# Schematic.net
KiCad netlist of a schematic drawn in EAGLE
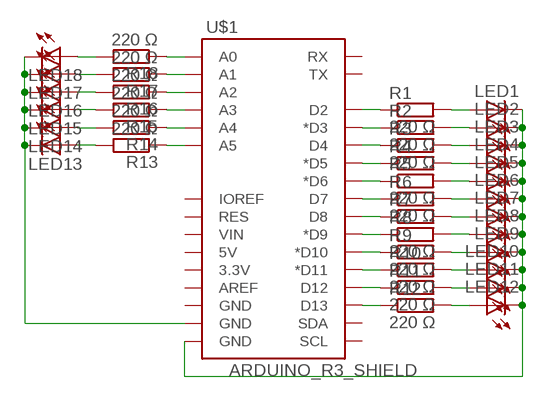
[diagram p0: schematic, sheet 1]

(export (version "E")
  (design (tool "Eeschema 10.0.6"))
  (components
    (comp (ref "LED1")
      (value "LED3MM")
      (footprint "eagle-import:LED3MM")
      (libsource (lib "eagle-import") (part "LED3MM"))
    )
    (comp (ref "LED2")
      (value "LED3MM")
      (footprint "eagle-import:LED3MM")
      (libsource (lib "eagle-import") (part "LED3MM"))
    )
    (comp (ref "LED3")
      (value "LED3MM")
      (footprint "eagle-import:LED3MM")
      (libsource (lib "eagle-import") (part "LED3MM"))
    )
    (comp (ref "LED4")
      (value "LED3MM")
      (footprint "eagle-import:LED3MM")
      (libsource (lib "eagle-import") (part "LED3MM"))
    )
    (comp (ref "LED5")
      (value "LED3MM")
      (footprint "eagle-import:LED3MM")
      (libsource (lib "eagle-import") (part "LED3MM"))
    )
    (comp (ref "LED6")
      (value "LED3MM")
      (footprint "eagle-import:LED3MM")
      (libsource (lib "eagle-import") (part "LED3MM"))
    )
    (comp (ref "LED7")
      (value "LED3MM")
      (footprint "eagle-import:LED3MM")
      (libsource (lib "eagle-import") (part "LED3MM"))
    )
    (comp (ref "LED8")
      (value "LED3MM")
      (footprint "eagle-import:LED3MM")
      (libsource (lib "eagle-import") (part "LED3MM"))
    )
    (comp (ref "LED9")
      (value "LED3MM")
      (footprint "eagle-import:LED3MM")
      (libsource (lib "eagle-import") (part "LED3MM"))
    )
    (comp (ref "LED10")
      (value "LED3MM")
      (footprint "eagle-import:LED3MM")
      (libsource (lib "eagle-import") (part "LED3MM"))
    )
    (comp (ref "LED11")
      (value "LED3MM")
      (footprint "eagle-import:LED3MM")
      (libsource (lib "eagle-import") (part "LED3MM"))
    )
    (comp (ref "LED12")
      (value "LED3MM")
      (footprint "eagle-import:LED3MM")
      (libsource (lib "eagle-import") (part "LED3MM"))
    )
    (comp (ref "LED13")
      (value "LED3MM")
      (footprint "eagle-import:LED3MM")
      (libsource (lib "eagle-import") (part "LED3MM"))
    )
    (comp (ref "LED14")
      (value "LED3MM")
      (footprint "eagle-import:LED3MM")
      (libsource (lib "eagle-import") (part "LED3MM"))
    )
    (comp (ref "LED15")
      (value "LED3MM")
      (footprint "eagle-import:LED3MM")
      (libsource (lib "eagle-import") (part "LED3MM"))
    )
    (comp (ref "LED16")
      (value "LED3MM")
      (footprint "eagle-import:LED3MM")
      (libsource (lib "eagle-import") (part "LED3MM"))
    )
    (comp (ref "LED17")
      (value "LED3MM")
      (footprint "eagle-import:LED3MM")
      (libsource (lib "eagle-import") (part "LED3MM"))
    )
    (comp (ref "LED18")
      (value "LED3MM")
      (footprint "eagle-import:LED3MM")
      (libsource (lib "eagle-import") (part "LED3MM"))
    )
    (comp (ref "R1")
      (value "220 Ω")
      (footprint "eagle-import:0204_7")
      (libsource (lib "eagle-import") (part "R-EU_0204/7"))
    )
    (comp (ref "R2")
      (value "220 Ω")
      (footprint "eagle-import:0204_7")
      (libsource (lib "eagle-import") (part "R-EU_0204/7"))
    )
    (comp (ref "R3")
      (value "220 Ω")
      (footprint "eagle-import:0204_7")
      (libsource (lib "eagle-import") (part "R-EU_0204/7"))
    )
    (comp (ref "R4")
      (value "R-EU_0204/7")
      (footprint "eagle-import:0204_7")
      (libsource (lib "eagle-import") (part "R-EU_0204/7"))
    )
    (comp (ref "R5")
      (value "220 Ω")
      (footprint "eagle-import:0204_7")
      (libsource (lib "eagle-import") (part "R-EU_0204/7"))
    )
    (comp (ref "R6")
      (value "220 Ω")
      (footprint "eagle-import:0204_7")
      (libsource (lib "eagle-import") (part "R-EU_0204/7"))
    )
    (comp (ref "R7")
      (value "R-EU_0204/7")
      (footprint "eagle-import:0204_7")
      (libsource (lib "eagle-import") (part "R-EU_0204/7"))
    )
    (comp (ref "R8")
      (value "220 Ω")
      (footprint "eagle-import:0204_7")
      (libsource (lib "eagle-import") (part "R-EU_0204/7"))
    )
    (comp (ref "R9")
      (value "220 Ω")
      (footprint "eagle-import:0204_7")
      (libsource (lib "eagle-import") (part "R-EU_0204/7"))
    )
    (comp (ref "R10")
      (value "220 Ω")
      (footprint "eagle-import:0204_7")
      (libsource (lib "eagle-import") (part "R-EU_0204/7"))
    )
    (comp (ref "R11")
      (value "220 Ω")
      (footprint "eagle-import:0204_7")
      (libsource (lib "eagle-import") (part "R-EU_0204/7"))
    )
    (comp (ref "R12")
      (value "220 Ω")
      (footprint "eagle-import:0204_7")
      (libsource (lib "eagle-import") (part "R-EU_0204/7"))
    )
    (comp (ref "R13")
      (value "220 Ω")
      (footprint "eagle-import:0204_7")
      (libsource (lib "eagle-import") (part "R-EU_0204/7"))
    )
    (comp (ref "R14")
      (value "220 Ω")
      (footprint "eagle-import:0204_7")
      (libsource (lib "eagle-import") (part "R-EU_0204/7"))
    )
    (comp (ref "R15")
      (value "220 Ω")
      (footprint "eagle-import:0204_7")
      (libsource (lib "eagle-import") (part "R-EU_0204/7"))
    )
    (comp (ref "R16")
      (value "220 Ω")
      (footprint "eagle-import:0204_7")
      (libsource (lib "eagle-import") (part "R-EU_0204/7"))
    )
    (comp (ref "R17")
      (value "220 Ω")
      (footprint "eagle-import:0204_7")
      (libsource (lib "eagle-import") (part "R-EU_0204/7"))
    )
    (comp (ref "R18")
      (value "220 Ω")
      (footprint "eagle-import:0204_7")
      (libsource (lib "eagle-import") (part "R-EU_0204/7"))
    )
    (comp (ref "U$1")
      (value "ARDUINO_R3_SHIELD")
      (footprint "eagle-import:UNO_R3_SHIELD")
      (libsource (lib "eagle-import") (part "ARDUINO_R3_SHIELD"))
    )
  )
  (nets
    (net (code "1") (name "Net-(LED1-C)") (class "Default")
      (node (ref "LED1") (pin "K") (pinfunction "C_K") (pintype "passive"))
      (node (ref "LED10") (pin "K") (pinfunction "C_K") (pintype "passive"))
      (node (ref "LED11") (pin "K") (pinfunction "C_K") (pintype "passive"))
      (node (ref "LED12") (pin "K") (pinfunction "C_K") (pintype "passive"))
      (node (ref "LED2") (pin "K") (pinfunction "C_K") (pintype "passive"))
      (node (ref "LED3") (pin "K") (pinfunction "C_K") (pintype "passive"))
      (node (ref "LED4") (pin "K") (pinfunction "C_K") (pintype "passive"))
      (node (ref "LED5") (pin "K") (pinfunction "C_K") (pintype "passive"))
      (node (ref "LED6") (pin "K") (pinfunction "C_K") (pintype "passive"))
      (node (ref "LED7") (pin "K") (pinfunction "C_K") (pintype "passive"))
      (node (ref "LED8") (pin "K") (pinfunction "C_K") (pintype "passive"))
      (node (ref "LED9") (pin "K") (pinfunction "C_K") (pintype "passive"))
      (node (ref "U$1") (pin "GND@0") (pinfunction "GND_GND@0") (pintype "bidirectional"))
    )
    (net (code "2") (name "Net-(LED1-PadA)") (class "Default")
      (node (ref "LED1") (pin "A") (pinfunction "A_A") (pintype "passive"))
      (node (ref "R1") (pin "2") (pinfunction "2_2") (pintype "passive"))
    )
    (net (code "3") (name "Net-(LED2-PadA)") (class "Default")
      (node (ref "LED2") (pin "A") (pinfunction "A_A") (pintype "passive"))
      (node (ref "R2") (pin "2") (pinfunction "2_2") (pintype "passive"))
    )
    (net (code "4") (name "Net-(LED3-PadA)") (class "Default")
      (node (ref "LED3") (pin "A") (pinfunction "A_A") (pintype "passive"))
      (node (ref "R3") (pin "2") (pinfunction "2_2") (pintype "passive"))
    )
    (net (code "5") (name "Net-(LED4-PadA)") (class "Default")
      (node (ref "LED4") (pin "A") (pinfunction "A_A") (pintype "passive"))
      (node (ref "R4") (pin "2") (pinfunction "2_2") (pintype "passive"))
    )
    (net (code "6") (name "Net-(LED5-PadA)") (class "Default")
      (node (ref "LED5") (pin "A") (pinfunction "A_A") (pintype "passive"))
      (node (ref "R5") (pin "2") (pinfunction "2_2") (pintype "passive"))
    )
    (net (code "7") (name "Net-(LED6-PadA)") (class "Default")
      (node (ref "LED6") (pin "A") (pinfunction "A_A") (pintype "passive"))
      (node (ref "R6") (pin "2") (pinfunction "2_2") (pintype "passive"))
    )
    (net (code "8") (name "Net-(LED7-PadA)") (class "Default")
      (node (ref "LED7") (pin "A") (pinfunction "A_A") (pintype "passive"))
      (node (ref "R7") (pin "2") (pinfunction "2_2") (pintype "passive"))
    )
    (net (code "9") (name "Net-(LED8-PadA)") (class "Default")
      (node (ref "LED8") (pin "A") (pinfunction "A_A") (pintype "passive"))
      (node (ref "R8") (pin "2") (pinfunction "2_2") (pintype "passive"))
    )
    (net (code "10") (name "Net-(LED9-PadA)") (class "Default")
      (node (ref "LED9") (pin "A") (pinfunction "A_A") (pintype "passive"))
      (node (ref "R9") (pin "2") (pinfunction "2_2") (pintype "passive"))
    )
    (net (code "11") (name "Net-(LED10-PadA)") (class "Default")
      (node (ref "LED10") (pin "A") (pinfunction "A_A") (pintype "passive"))
      (node (ref "R10") (pin "2") (pinfunction "2_2") (pintype "passive"))
    )
    (net (code "12") (name "Net-(LED11-PadA)") (class "Default")
      (node (ref "LED11") (pin "A") (pinfunction "A_A") (pintype "passive"))
      (node (ref "R11") (pin "2") (pinfunction "2_2") (pintype "passive"))
    )
    (net (code "13") (name "Net-(LED12-PadA)") (class "Default")
      (node (ref "LED12") (pin "A") (pinfunction "A_A") (pintype "passive"))
      (node (ref "R12") (pin "2") (pinfunction "2_2") (pintype "passive"))
    )
    (net (code "14") (name "Net-(LED13-C)") (class "Default")
      (node (ref "LED13") (pin "K") (pinfunction "C_K") (pintype "passive"))
      (node (ref "LED14") (pin "K") (pinfunction "C_K") (pintype "passive"))
      (node (ref "LED15") (pin "K") (pinfunction "C_K") (pintype "passive"))
      (node (ref "LED16") (pin "K") (pinfunction "C_K") (pintype "passive"))
      (node (ref "LED17") (pin "K") (pinfunction "C_K") (pintype "passive"))
      (node (ref "LED18") (pin "K") (pinfunction "C_K") (pintype "passive"))
      (node (ref "U$1") (pin "GND@1") (pinfunction "GND_GND@1") (pintype "bidirectional"))
    )
    (net (code "15") (name "Net-(LED13-PadA)") (class "Default")
      (node (ref "LED13") (pin "A") (pinfunction "A_A") (pintype "passive"))
      (node (ref "R13") (pin "2") (pinfunction "2_2") (pintype "passive"))
    )
    (net (code "16") (name "Net-(LED14-PadA)") (class "Default")
      (node (ref "LED14") (pin "A") (pinfunction "A_A") (pintype "passive"))
      (node (ref "R14") (pin "2") (pinfunction "2_2") (pintype "passive"))
    )
    (net (code "17") (name "Net-(LED15-PadA)") (class "Default")
      (node (ref "LED15") (pin "A") (pinfunction "A_A") (pintype "passive"))
      (node (ref "R15") (pin "2") (pinfunction "2_2") (pintype "passive"))
    )
    (net (code "18") (name "Net-(LED16-PadA)") (class "Default")
      (node (ref "LED16") (pin "A") (pinfunction "A_A") (pintype "passive"))
      (node (ref "R16") (pin "2") (pinfunction "2_2") (pintype "passive"))
    )
    (net (code "19") (name "Net-(LED17-PadA)") (class "Default")
      (node (ref "LED17") (pin "A") (pinfunction "A_A") (pintype "passive"))
      (node (ref "R17") (pin "2") (pinfunction "2_2") (pintype "passive"))
    )
    (net (code "20") (name "Net-(LED18-PadA)") (class "Default")
      (node (ref "LED18") (pin "A") (pinfunction "A_A") (pintype "passive"))
      (node (ref "R18") (pin "2") (pinfunction "2_2") (pintype "passive"))
    )
    (net (code "21") (name "Net-(R1-Pad1)") (class "Default")
      (node (ref "R1") (pin "1") (pinfunction "1_1") (pintype "passive"))
      (node (ref "U$1") (pin "D2") (pinfunction "D2_D2") (pintype "bidirectional"))
    )
    (net (code "22") (name "Net-(R3-Pad1)") (class "Default")
      (node (ref "R3") (pin "1") (pinfunction "1_1") (pintype "passive"))
      (node (ref "U$1") (pin "D4") (pinfunction "D4_D4") (pintype "bidirectional"))
    )
    (net (code "23") (name "Net-(R6-Pad1)") (class "Default")
      (node (ref "R6") (pin "1") (pinfunction "1_1") (pintype "passive"))
      (node (ref "U$1") (pin "D7") (pinfunction "D7_D7") (pintype "bidirectional"))
    )
    (net (code "24") (name "Net-(R7-Pad1)") (class "Default")
      (node (ref "R7") (pin "1") (pinfunction "1_1") (pintype "passive"))
      (node (ref "U$1") (pin "D8") (pinfunction "D8_D8") (pintype "bidirectional"))
    )
    (net (code "25") (name "Net-(R11-Pad1)") (class "Default")
      (node (ref "R11") (pin "1") (pinfunction "1_1") (pintype "passive"))
      (node (ref "U$1") (pin "D12") (pinfunction "D12_D12") (pintype "bidirectional"))
    )
    (net (code "26") (name "Net-(R12-Pad1)") (class "Default")
      (node (ref "R12") (pin "1") (pinfunction "1_1") (pintype "passive"))
      (node (ref "U$1") (pin "D13") (pinfunction "D13_D13") (pintype "bidirectional"))
    )
    (net (code "27") (name "Net-(R13-Pad1)") (class "Default")
      (node (ref "R13") (pin "1") (pinfunction "1_1") (pintype "passive"))
      (node (ref "U$1") (pin "A5") (pinfunction "A5_A5") (pintype "bidirectional"))
    )
    (net (code "28") (name "Net-(R14-Pad1)") (class "Default")
      (node (ref "R14") (pin "1") (pinfunction "1_1") (pintype "passive"))
      (node (ref "U$1") (pin "A4") (pinfunction "A4_A4") (pintype "bidirectional"))
    )
    (net (code "29") (name "Net-(R15-Pad1)") (class "Default")
      (node (ref "R15") (pin "1") (pinfunction "1_1") (pintype "passive"))
      (node (ref "U$1") (pin "A3") (pinfunction "A3_A3") (pintype "bidirectional"))
    )
    (net (code "30") (name "Net-(R16-Pad1)") (class "Default")
      (node (ref "R16") (pin "1") (pinfunction "1_1") (pintype "passive"))
      (node (ref "U$1") (pin "A2") (pinfunction "A2_A2") (pintype "bidirectional"))
    )
    (net (code "31") (name "Net-(R17-Pad1)") (class "Default")
      (node (ref "R17") (pin "1") (pinfunction "1_1") (pintype "passive"))
      (node (ref "U$1") (pin "A1") (pinfunction "A1_A1") (pintype "bidirectional"))
    )
    (net (code "32") (name "Net-(R18-Pad1)") (class "Default")
      (node (ref "R18") (pin "1") (pinfunction "1_1") (pintype "passive"))
      (node (ref "U$1") (pin "A0") (pinfunction "A0_A0") (pintype "bidirectional"))
    )
    (net (code "33") (name "Net-(U$1-*D3)") (class "Default")
      (node (ref "R2") (pin "1") (pinfunction "1_1") (pintype "passive"))
      (node (ref "U$1") (pin "D3") (pinfunction "*D3_D3") (pintype "bidirectional"))
    )
    (net (code "34") (name "Net-(U$1-*D5)") (class "Default")
      (node (ref "R4") (pin "1") (pinfunction "1_1") (pintype "passive"))
      (node (ref "U$1") (pin "D5") (pinfunction "*D5_D5") (pintype "bidirectional"))
    )
    (net (code "35") (name "Net-(U$1-*D6)") (class "Default")
      (node (ref "R5") (pin "1") (pinfunction "1_1") (pintype "passive"))
      (node (ref "U$1") (pin "D6") (pinfunction "*D6_D6") (pintype "bidirectional"))
    )
    (net (code "36") (name "Net-(U$1-*D9)") (class "Default")
      (node (ref "R8") (pin "1") (pinfunction "1_1") (pintype "passive"))
      (node (ref "U$1") (pin "D9") (pinfunction "*D9_D9") (pintype "bidirectional"))
    )
    (net (code "37") (name "Net-(U$1-*D10)") (class "Default")
      (node (ref "R9") (pin "1") (pinfunction "1_1") (pintype "passive"))
      (node (ref "U$1") (pin "D10") (pinfunction "*D10_D10") (pintype "bidirectional"))
    )
    (net (code "38") (name "Net-(U$1-*D11)") (class "Default")
      (node (ref "R10") (pin "1") (pinfunction "1_1") (pintype "passive"))
      (node (ref "U$1") (pin "D11") (pinfunction "*D11_D11") (pintype "bidirectional"))
    )
    (net (code "39") (name "unconnected-(U$1-GND-PadGND@2)") (class "Default")
      (node (ref "U$1") (pin "GND@2") (pinfunction "GND_GND@2") (pintype "bidirectional"))
    )
    (net (code "40") (name "unconnected-(U$1-Pad3.3V)") (class "Default")
      (node (ref "U$1") (pin "3.3V") (pinfunction "3.3V_3.3V") (pintype "bidirectional"))
    )
    (net (code "41") (name "unconnected-(U$1-Pad5V)") (class "Default")
      (node (ref "U$1") (pin "5V") (pinfunction "5V_5V") (pintype "bidirectional"))
    )
    (net (code "42") (name "unconnected-(U$1-PadAREF)") (class "Default")
      (node (ref "U$1") (pin "AREF") (pinfunction "AREF_AREF") (pintype "bidirectional"))
    )
    (net (code "43") (name "unconnected-(U$1-PadIOREF)") (class "Default")
      (node (ref "U$1") (pin "IOREF") (pinfunction "IOREF_IOREF") (pintype "bidirectional"))
    )
    (net (code "44") (name "unconnected-(U$1-PadRES)") (class "Default")
      (node (ref "U$1") (pin "RES") (pinfunction "RES_RES") (pintype "bidirectional"))
    )
    (net (code "45") (name "unconnected-(U$1-PadRX)") (class "Default")
      (node (ref "U$1") (pin "RX") (pinfunction "RX_RX") (pintype "bidirectional"))
    )
    (net (code "46") (name "unconnected-(U$1-PadSCL)") (class "Default")
      (node (ref "U$1") (pin "SCL") (pinfunction "SCL_SCL") (pintype "bidirectional"))
    )
    (net (code "47") (name "unconnected-(U$1-PadSDA)") (class "Default")
      (node (ref "U$1") (pin "SDA") (pinfunction "SDA_SDA") (pintype "bidirectional"))
    )
    (net (code "48") (name "unconnected-(U$1-PadTX)") (class "Default")
      (node (ref "U$1") (pin "TX") (pinfunction "TX_TX") (pintype "bidirectional"))
    )
    (net (code "49") (name "unconnected-(U$1-PadVIN)") (class "Default")
      (node (ref "U$1") (pin "VIN") (pinfunction "VIN_VIN") (pintype "bidirectional"))
    )
  )
)
